# openSX70_ALADDIN_V391_20180125.net
KiCad netlist of a schematic drawn in EAGLE
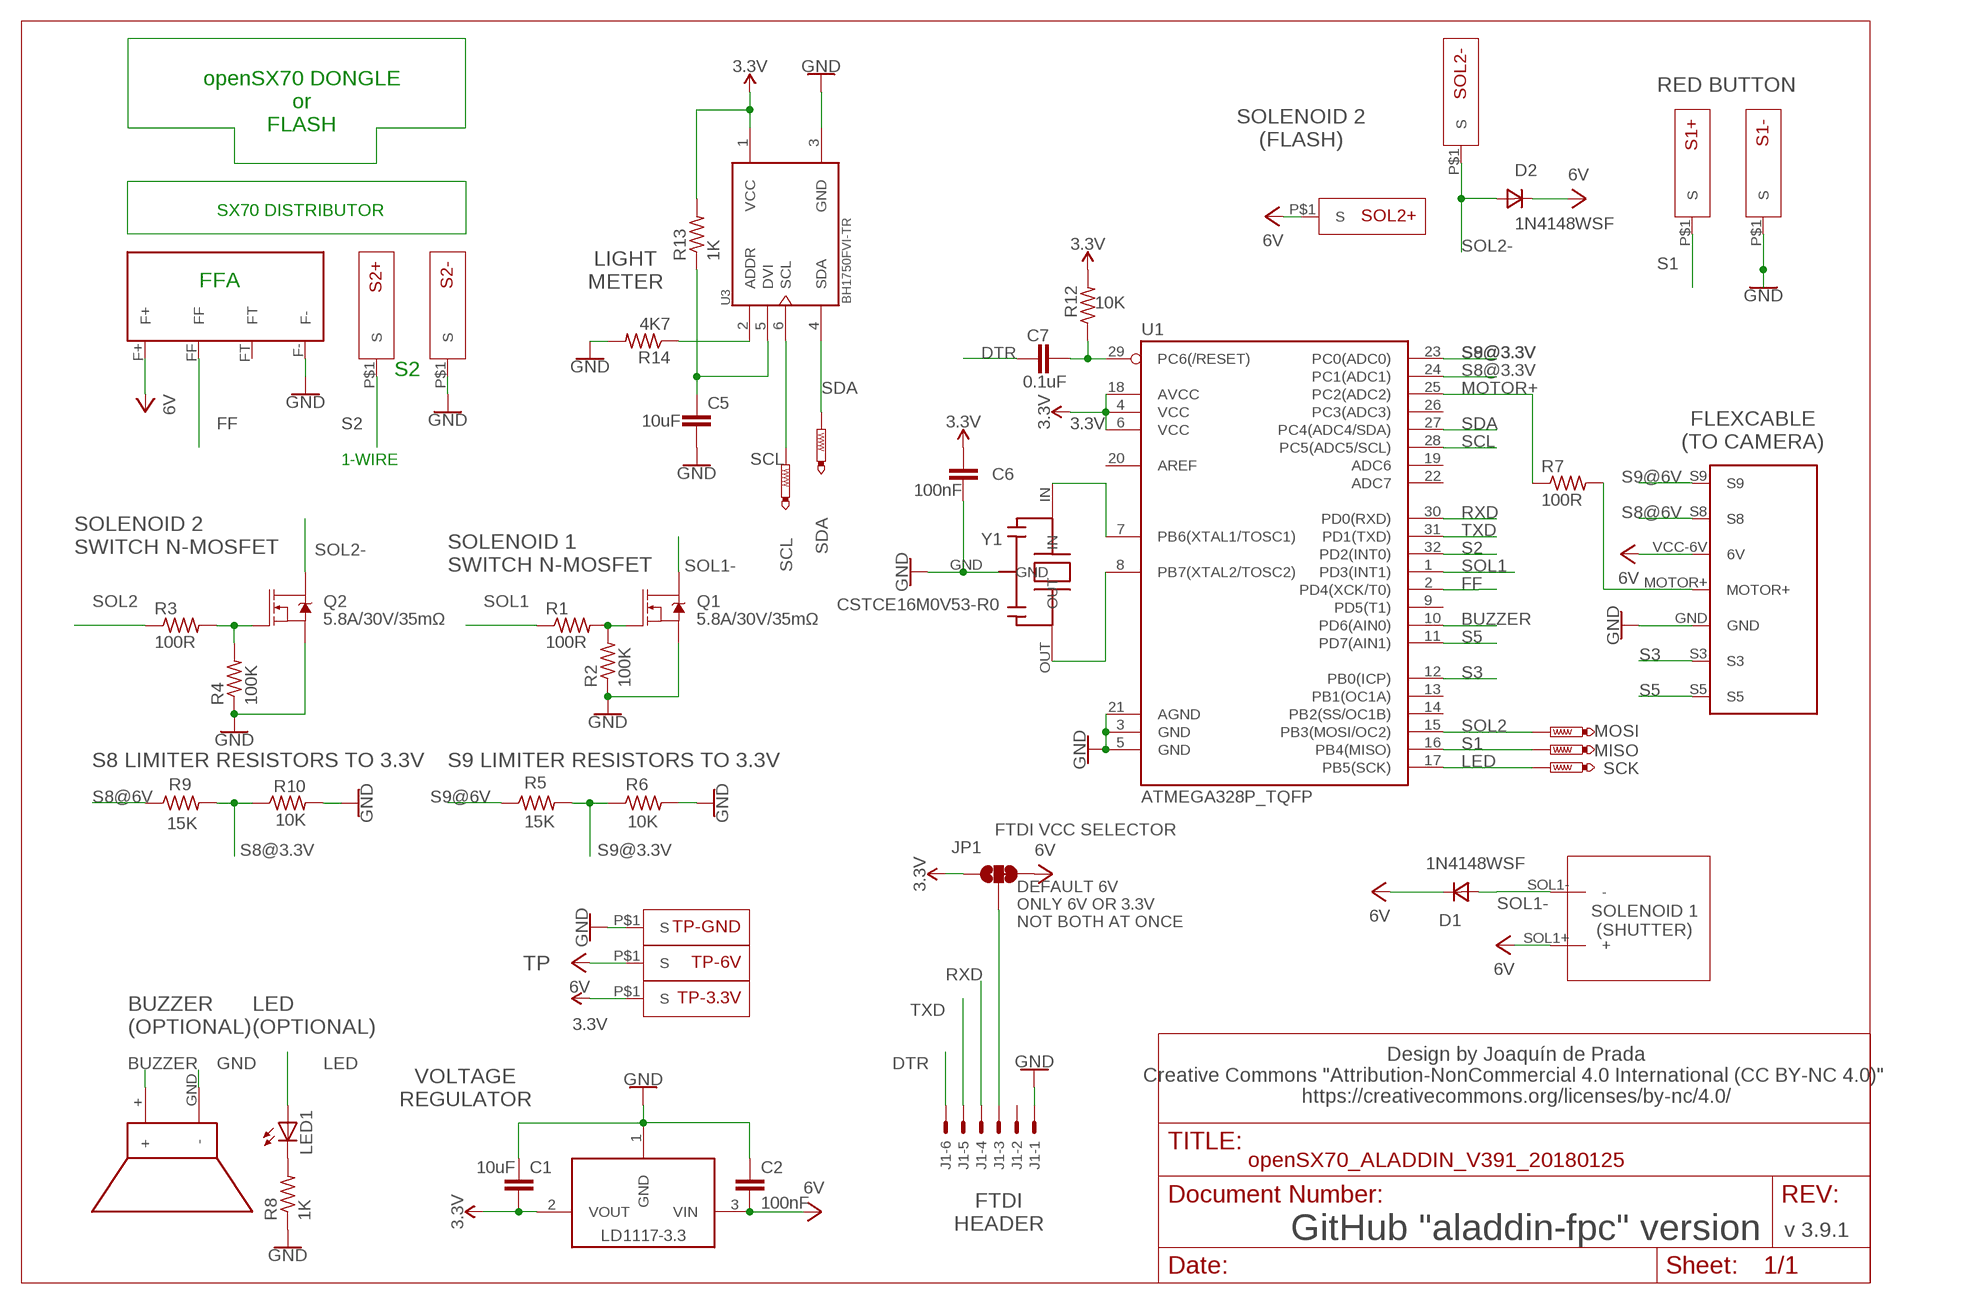
[diagram p0: schematic, sheet 1]

(export (version "E")
  (design (tool "Eeschema 10.0.6"))
  (components
    (comp (ref "BUZZ1")
      (value "CSET8-5G")
      (footprint "eagle-import:CSET8-5G_PACKAGE")
      (libsource (lib "eagle-import") (part "CSET8-5G"))
    )
    (comp (ref "C1")
      (value "10uF")
      (footprint "eagle-import:0603")
      (libsource (lib "eagle-import") (part "10UF-0603-6.3V-20%"))
    )
    (comp (ref "C2")
      (value "100nF")
      (footprint "eagle-import:C0603K")
      (libsource (lib "eagle-import") (part "C-EUC0603K"))
    )
    (comp (ref "C5")
      (value "10uF")
      (footprint "eagle-import:0603")
      (libsource (lib "eagle-import") (part "10UF-0603-6.3V-20%"))
    )
    (comp (ref "C6")
      (value "100nF")
      (footprint "eagle-import:C0603")
      (libsource (lib "eagle-import") (part "C-EUC0603"))
    )
    (comp (ref "C7")
      (value "0.1uF")
      (footprint "eagle-import:0603")
      (libsource (lib "eagle-import") (part "0.1UF-0603-25V-(+80/-20%)"))
    )
    (comp (ref "D1")
      (value "1N4148WSF")
      (footprint "eagle-import:SOD323")
      (fields (field (name "MPN") "CDSOD323-T05C"))
      (libsource (lib "eagle-import") (part "DSOD323"))
    )
    (comp (ref "D2")
      (value "1N4148WSF")
      (footprint "eagle-import:SOD323")
      (fields (field (name "MPN") "CDSOD323-T05C"))
      (libsource (lib "eagle-import") (part "DSOD323"))
    )
    (comp (ref "J1")
      (value "GND")
      (footprint "eagle-import:XF2L-0625-1")
      (fields (field (name "MF") "OMRON COMPONENTS USA") (field (name "MPN") "XF2L-0625-1"))
      (libsource (lib "eagle-import") (part "XF2-06?25-1L"))
    )
    (comp (ref "JP1")
      (value "FTDI VCC SELECTOR")
      (footprint "eagle-import:SMT-JUMPER_3_1-NC_TRACE_SILK")
      (libsource (lib "eagle-import") (part "JUMPER-SMT_3_1-NC_TRACE_SILK"))
    )
    (comp (ref "LD11172.5V")
      (value "LD1117 2.5V")
      (footprint "eagle-import:SOT223")
      (fields (field (name "MF") "Advanced Monolithic Systems") (field (name "MP") "AMS1117-5.0"))
      (libsource (lib "eagle-import") (part "LD1117-3.3"))
    )
    (comp (ref "LED1")
      (value "LEDCHIPLED_0805")
      (footprint "eagle-import:CHIPLED_0805")
      (libsource (lib "eagle-import") (part "LEDCHIPLED_0805"))
    )
    (comp (ref "MISO")
      (value "PTR1TP08R")
      (footprint "eagle-import:TP08R")
      (libsource (lib "eagle-import") (part "PTR1TP08R"))
    )
    (comp (ref "MOSI")
      (value "PTR1TP08R")
      (footprint "eagle-import:TP08R")
      (libsource (lib "eagle-import") (part "PTR1TP08R"))
    )
    (comp (ref "Q1")
      (value "5.8A/30V/35mΩ")
      (footprint "eagle-import:SOT23-3")
      (libsource (lib "eagle-import") (part "MOSFET-NCH-AO3404A"))
    )
    (comp (ref "Q2")
      (value "5.8A/30V/35mΩ")
      (footprint "eagle-import:SOT23-3")
      (libsource (lib "eagle-import") (part "MOSFET-NCH-AO3404A"))
    )
    (comp (ref "R1")
      (value "100R")
      (footprint "eagle-import:R0603")
      (libsource (lib "eagle-import") (part "R-US_R0603"))
    )
    (comp (ref "R2")
      (value "100K")
      (footprint "eagle-import:R0603")
      (libsource (lib "eagle-import") (part "R-US_R0603"))
    )
    (comp (ref "R3")
      (value "100R")
      (footprint "eagle-import:R0603")
      (libsource (lib "eagle-import") (part "R-US_R0603"))
    )
    (comp (ref "R4")
      (value "100K")
      (footprint "eagle-import:R0603")
      (libsource (lib "eagle-import") (part "R-US_R0603"))
    )
    (comp (ref "R5")
      (value "15K")
      (footprint "eagle-import:R0603")
      (libsource (lib "eagle-import") (part "R-US_R0603"))
    )
    (comp (ref "R6")
      (value "10K")
      (footprint "eagle-import:R0603")
      (libsource (lib "eagle-import") (part "R-US_R0603"))
    )
    (comp (ref "R7")
      (value "100R")
      (footprint "eagle-import:R0603")
      (libsource (lib "eagle-import") (part "R-US_R0603"))
    )
    (comp (ref "R8")
      (value "1K")
      (footprint "eagle-import:R0603")
      (libsource (lib "eagle-import") (part "R-US_R0603"))
    )
    (comp (ref "R9")
      (value "15K")
      (footprint "eagle-import:R0603")
      (libsource (lib "eagle-import") (part "R-US_R0603"))
    )
    (comp (ref "R10")
      (value "10K")
      (footprint "eagle-import:R0603")
      (libsource (lib "eagle-import") (part "R-US_R0603"))
    )
    (comp (ref "R12")
      (value "10K")
      (footprint "eagle-import:R0603")
      (libsource (lib "eagle-import") (part "R-US_R0603"))
    )
    (comp (ref "R13")
      (value "1K")
      (footprint "eagle-import:R0603")
      (libsource (lib "eagle-import") (part "R-US_R0603"))
    )
    (comp (ref "R14")
      (value "4K7")
      (footprint "eagle-import:R0603")
      (libsource (lib "eagle-import") (part "R-US_R0603"))
    )
    (comp (ref "S1+")
      (value "SX70-S-PAD-NEW")
      (footprint "eagle-import:SX70-S-PAD2")
      (libsource (lib "eagle-import") (part "SX70-S-PAD-NEW"))
    )
    (comp (ref "S1-")
      (value "SX70-S-PAD-NEW")
      (footprint "eagle-import:SX70-S-PAD2")
      (libsource (lib "eagle-import") (part "SX70-S-PAD-NEW"))
    )
    (comp (ref "S2+")
      (value "SX70-S-PAD-NEW")
      (footprint "eagle-import:SX70-S-PAD2")
      (libsource (lib "eagle-import") (part "SX70-S-PAD-NEW"))
    )
    (comp (ref "S2-")
      (value "SX70-S-PAD-NEW")
      (footprint "eagle-import:SX70-S-PAD2")
      (libsource (lib "eagle-import") (part "SX70-S-PAD-NEW"))
    )
    (comp (ref "SCK")
      (value "PTR1TP08R")
      (footprint "eagle-import:TP08R")
      (libsource (lib "eagle-import") (part "PTR1TP08R"))
    )
    (comp (ref "SCL")
      (value "PTR1TP08R")
      (footprint "eagle-import:TP08R")
      (libsource (lib "eagle-import") (part "PTR1TP08R"))
    )
    (comp (ref "SDA")
      (value "PTR1TP08R")
      (footprint "eagle-import:TP08R")
      (libsource (lib "eagle-import") (part "PTR1TP08R"))
    )
    (comp (ref "SOL1")
      (value "SX70-SOLENOID1-2PADS")
      (footprint "eagle-import:SX70-SOLENOID1-2")
      (libsource (lib "eagle-import") (part "SX70-SOLENOID1-2PADS"))
    )
    (comp (ref "SOL2+")
      (value "SX70-S-PAD-NEW")
      (footprint "eagle-import:SX70-S-PAD2")
      (libsource (lib "eagle-import") (part "SX70-S-PAD-NEW"))
    )
    (comp (ref "SOL2-")
      (value "SX70-S-PAD-NEW")
      (footprint "eagle-import:SX70-S-PAD2")
      (libsource (lib "eagle-import") (part "SX70-S-PAD-NEW"))
    )
    (comp (ref "TP-3.3V")
      (value "SX70-S-PAD-NEW")
      (footprint "eagle-import:SX70-S-PAD2")
      (libsource (lib "eagle-import") (part "SX70-S-PAD-NEW"))
    )
    (comp (ref "TP-6V")
      (value "SX70-S-PAD-NEW")
      (footprint "eagle-import:SX70-S-PAD2")
      (libsource (lib "eagle-import") (part "SX70-S-PAD-NEW"))
    )
    (comp (ref "TP-GND")
      (value "SX70-S-PAD-NEW")
      (footprint "eagle-import:SX70-S-PAD2")
      (libsource (lib "eagle-import") (part "SX70-S-PAD-NEW"))
    )
    (comp (ref "U$1")
      (value "SX70-7-PAD")
      (footprint "eagle-import:SX70-7-PAD")
      (libsource (lib "eagle-import") (part "SX70-7-PAD"))
    )
    (comp (ref "U$2")
      (value "FFA")
      (footprint "eagle-import:FFA-PAD-PACKAGE")
      (libsource (lib "eagle-import") (part "SX70-FFA-PAD"))
    )
    (comp (ref "U1")
      (value "ATMEGA328P_TQFP")
      (footprint "eagle-import:TQFP32-08")
      (libsource (lib "eagle-import") (part "ATMEGA328P_TQFP"))
    )
    (comp (ref "U3")
      (value "BH1750FVI-TR")
      (footprint "eagle-import:SOTFL50P300X75-6N")
      (fields (field (name "MF") "Rohm"))
      (libsource (lib "eagle-import") (part "BH1750FVI-TR"))
    )
    (comp (ref "Y1")
      (value "CSTCE16M0V53-R0")
      (footprint "eagle-import:CFP95P160X100-3N")
      (fields (field (name "MF") "Murata"))
      (libsource (lib "eagle-import") (part "CSTCE16M0V53-R0"))
    )
  )
  (nets
    (net (code "1") (name "/BUZZER") (class "Default")
      (node (ref "BUZZ1") (pin "+") (pinfunction "+_+") (pintype "bidirectional"))
      (node (ref "U1") (pin "10") (pinfunction "PD6(AIN0)_10") (pintype "bidirectional"))
    )
    (net (code "2") (name "/DTR") (class "Default")
      (node (ref "C7") (pin "1") (pinfunction "1_1") (pintype "passive"))
      (node (ref "J1") (pin "6") (pinfunction "MS_6") (pintype "passive"))
    )
    (net (code "3") (name "/FF") (class "Default")
      (node (ref "U$2") (pin "FF") (pinfunction "FF_FF") (pintype "bidirectional"))
      (node (ref "U1") (pin "2") (pinfunction "PD4(XCK/T0)_2") (pintype "bidirectional"))
    )
    (net (code "4") (name "/LED") (class "Default")
      (node (ref "LED1") (pin "A") (pinfunction "A_A") (pintype "passive"))
      (node (ref "SCK") (pin "TP") (pinfunction "TP_TP") (pintype "input"))
      (node (ref "U1") (pin "17") (pinfunction "PB5(SCK)_17") (pintype "bidirectional"))
    )
    (net (code "5") (name "/MOTOR+") (class "Default")
      (node (ref "R7") (pin "1") (pinfunction "1_1") (pintype "passive"))
      (node (ref "U1") (pin "25") (pinfunction "PC2(ADC2)_25") (pintype "bidirectional"))
    )
    (net (code "6") (name "/RXD") (class "Default")
      (node (ref "J1") (pin "4") (pinfunction "MS_4") (pintype "passive"))
      (node (ref "U1") (pin "30") (pinfunction "PD0(RXD)_30") (pintype "bidirectional"))
    )
    (net (code "7") (name "/S1") (class "Default")
      (node (ref "MISO") (pin "TP") (pinfunction "TP_TP") (pintype "input"))
      (node (ref "S1+") (pin "P$1") (pinfunction "S_P$1") (pintype "bidirectional"))
      (node (ref "U1") (pin "16") (pinfunction "PB4(MISO)_16") (pintype "bidirectional"))
    )
    (net (code "8") (name "/S2") (class "Default")
      (node (ref "S2+") (pin "P$1") (pinfunction "S_P$1") (pintype "bidirectional"))
      (node (ref "U1") (pin "32") (pinfunction "PD2(INT0)_32") (pintype "bidirectional"))
    )
    (net (code "9") (name "/S3") (class "Default")
      (node (ref "U$1") (pin "S3") (pinfunction "S3_S3") (pintype "bidirectional"))
      (node (ref "U1") (pin "12") (pinfunction "PB0(ICP)_12") (pintype "bidirectional"))
    )
    (net (code "10") (name "/S5") (class "Default")
      (node (ref "U$1") (pin "S5") (pinfunction "S5_S5") (pintype "bidirectional"))
      (node (ref "U1") (pin "11") (pinfunction "PD7(AIN1)_11") (pintype "bidirectional"))
    )
    (net (code "11") (name "/S8@3.3V") (class "Default")
      (node (ref "R10") (pin "1") (pinfunction "1_1") (pintype "passive"))
      (node (ref "R9") (pin "2") (pinfunction "2_2") (pintype "passive"))
      (node (ref "U1") (pin "24") (pinfunction "PC1(ADC1)_24") (pintype "bidirectional"))
    )
    (net (code "12") (name "/S8@6V") (class "Default")
      (node (ref "R9") (pin "1") (pinfunction "1_1") (pintype "passive"))
      (node (ref "U$1") (pin "S8") (pinfunction "S8_S8") (pintype "bidirectional"))
    )
    (net (code "13") (name "/S9@3.3V") (class "Default")
      (node (ref "R5") (pin "2") (pinfunction "2_2") (pintype "passive"))
      (node (ref "R6") (pin "1") (pinfunction "1_1") (pintype "passive"))
      (node (ref "U1") (pin "23") (pinfunction "PC0(ADC0)_23") (pintype "bidirectional"))
    )
    (net (code "14") (name "/S9@6V") (class "Default")
      (node (ref "R5") (pin "1") (pinfunction "1_1") (pintype "passive"))
      (node (ref "U$1") (pin "S9") (pinfunction "S9_S9") (pintype "bidirectional"))
    )
    (net (code "15") (name "/SCL") (class "Default")
      (node (ref "SCL") (pin "TP") (pinfunction "TP_TP") (pintype "input"))
      (node (ref "U1") (pin "28") (pinfunction "PC5(ADC5/SCL)_28") (pintype "bidirectional"))
      (node (ref "U3") (pin "6") (pinfunction "SCL_6") (pintype "input"))
    )
    (net (code "16") (name "/SDA") (class "Default")
      (node (ref "SDA") (pin "TP") (pinfunction "TP_TP") (pintype "input"))
      (node (ref "U1") (pin "27") (pinfunction "PC4(ADC4/SDA)_27") (pintype "bidirectional"))
      (node (ref "U3") (pin "4") (pinfunction "SDA_4") (pintype "bidirectional"))
    )
    (net (code "17") (name "/SOL1") (class "Default")
      (node (ref "R1") (pin "1") (pinfunction "1_1") (pintype "passive"))
      (node (ref "U1") (pin "1") (pinfunction "PD3(INT1)_1") (pintype "bidirectional"))
    )
    (net (code "18") (name "/SOL1-") (class "Default")
      (node (ref "D1") (pin "2") (pinfunction "A_2") (pintype "passive"))
      (node (ref "Q1") (pin "3") (pinfunction "D_3") (pintype "bidirectional"))
      (node (ref "SOL1") (pin "SOL1-") (pinfunction "-_SOL1-") (pintype "bidirectional"))
    )
    (net (code "19") (name "/SOL2") (class "Default")
      (node (ref "MOSI") (pin "TP") (pinfunction "TP_TP") (pintype "input"))
      (node (ref "R3") (pin "1") (pinfunction "1_1") (pintype "passive"))
      (node (ref "U1") (pin "15") (pinfunction "PB3(MOSI/OC2)_15") (pintype "bidirectional"))
    )
    (net (code "20") (name "/SOL2-") (class "Default")
      (node (ref "D2") (pin "2") (pinfunction "A_2") (pintype "passive"))
      (node (ref "Q2") (pin "3") (pinfunction "D_3") (pintype "bidirectional"))
      (node (ref "SOL2-") (pin "P$1") (pinfunction "S_P$1") (pintype "bidirectional"))
    )
    (net (code "21") (name "/TXD") (class "Default")
      (node (ref "J1") (pin "5") (pinfunction "MS_5") (pintype "passive"))
      (node (ref "U1") (pin "31") (pinfunction "PD1(TXD)_31") (pintype "bidirectional"))
    )
    (net (code "22") (name "3.3V") (class "Default")
      (node (ref "C1") (pin "2") (pinfunction "2_2") (pintype "passive"))
      (node (ref "C6") (pin "1") (pinfunction "1_1") (pintype "passive"))
      (node (ref "JP1") (pin "1") (pinfunction "1_1") (pintype "passive"))
      (node (ref "LD11172.5V") (pin "2") (pinfunction "VOUT_2") (pintype "bidirectional"))
      (node (ref "R12") (pin "2") (pinfunction "2_2") (pintype "passive"))
      (node (ref "R13") (pin "2") (pinfunction "2_2") (pintype "passive"))
      (node (ref "TP-3.3V") (pin "P$1") (pinfunction "S_P$1") (pintype "bidirectional"))
      (node (ref "U1") (pin "18") (pinfunction "AVCC_18") (pintype "bidirectional"))
      (node (ref "U1") (pin "4") (pinfunction "VCC_4") (pintype "bidirectional"))
      (node (ref "U1") (pin "6") (pinfunction "VCC_6") (pintype "bidirectional"))
      (node (ref "U3") (pin "1") (pinfunction "VCC_1") (pintype "power_in"))
    )
    (net (code "23") (name "6V") (class "Default")
      (node (ref "C2") (pin "2") (pinfunction "2_2") (pintype "passive"))
      (node (ref "D1") (pin "1") (pinfunction "C_1") (pintype "passive"))
      (node (ref "D2") (pin "1") (pinfunction "C_1") (pintype "passive"))
      (node (ref "JP1") (pin "3") (pinfunction "3_3") (pintype "passive"))
      (node (ref "LD11172.5V") (pin "3") (pinfunction "VIN_3") (pintype "bidirectional"))
      (node (ref "SOL1") (pin "SOL1+") (pinfunction "+_SOL1+") (pintype "bidirectional"))
      (node (ref "SOL2+") (pin "P$1") (pinfunction "S_P$1") (pintype "bidirectional"))
      (node (ref "TP-6V") (pin "P$1") (pinfunction "S_P$1") (pintype "bidirectional"))
      (node (ref "U$1") (pin "VCC-6V") (pinfunction "6V_VCC-6V") (pintype "bidirectional"))
      (node (ref "U$2") (pin "F+") (pinfunction "F+_F+") (pintype "bidirectional"))
    )
    (net (code "24") (name "GND") (class "Default")
      (node (ref "BUZZ1") (pin "GND") (pinfunction "-_GND") (pintype "bidirectional"))
      (node (ref "C1") (pin "1") (pinfunction "1_1") (pintype "passive"))
      (node (ref "C2") (pin "1") (pinfunction "1_1") (pintype "passive"))
      (node (ref "C5") (pin "2") (pinfunction "2_2") (pintype "passive"))
      (node (ref "C6") (pin "2") (pinfunction "2_2") (pintype "passive"))
      (node (ref "J1") (pin "1") (pinfunction "MS_1") (pintype "passive"))
      (node (ref "LD11172.5V") (pin "1") (pinfunction "GND_1") (pintype "bidirectional"))
      (node (ref "Q1") (pin "2") (pinfunction "S_2") (pintype "bidirectional"))
      (node (ref "Q2") (pin "2") (pinfunction "S_2") (pintype "bidirectional"))
      (node (ref "R10") (pin "2") (pinfunction "2_2") (pintype "passive"))
      (node (ref "R14") (pin "2") (pinfunction "2_2") (pintype "passive"))
      (node (ref "R2") (pin "1") (pinfunction "1_1") (pintype "passive"))
      (node (ref "R4") (pin "1") (pinfunction "1_1") (pintype "passive"))
      (node (ref "R6") (pin "2") (pinfunction "2_2") (pintype "passive"))
      (node (ref "R8") (pin "1") (pinfunction "1_1") (pintype "passive"))
      (node (ref "S1-") (pin "P$1") (pinfunction "S_P$1") (pintype "bidirectional"))
      (node (ref "S2-") (pin "P$1") (pinfunction "S_P$1") (pintype "bidirectional"))
      (node (ref "TP-GND") (pin "P$1") (pinfunction "S_P$1") (pintype "bidirectional"))
      (node (ref "U$1") (pin "GND") (pinfunction "GND_GND") (pintype "bidirectional"))
      (node (ref "U$2") (pin "F-") (pinfunction "F-_F-") (pintype "bidirectional"))
      (node (ref "U1") (pin "21") (pinfunction "AGND_21") (pintype "bidirectional"))
      (node (ref "U1") (pin "3") (pinfunction "GND_3") (pintype "bidirectional"))
      (node (ref "U1") (pin "5") (pinfunction "GND_5") (pintype "bidirectional"))
      (node (ref "U3") (pin "3") (pinfunction "GND_3") (pintype "power_in"))
      (node (ref "Y1") (pin "GND") (pinfunction "GND_GND") (pintype "passive"))
    )
    (net (code "25") (name "Net-(J1C-MS)") (class "Default")
      (node (ref "J1") (pin "3") (pinfunction "MS_3") (pintype "passive"))
      (node (ref "JP1") (pin "2") (pinfunction "2_2") (pintype "passive"))
    )
    (net (code "26") (name "Net-(LED1-PadC)") (class "Default")
      (node (ref "LED1") (pin "C") (pinfunction "C_C") (pintype "passive"))
      (node (ref "R8") (pin "2") (pinfunction "2_2") (pintype "passive"))
    )
    (net (code "27") (name "Net-(Q1-G)") (class "Default")
      (node (ref "Q1") (pin "1") (pinfunction "G_1") (pintype "bidirectional"))
      (node (ref "R1") (pin "2") (pinfunction "2_2") (pintype "passive"))
      (node (ref "R2") (pin "2") (pinfunction "2_2") (pintype "passive"))
    )
    (net (code "28") (name "Net-(Q2-G)") (class "Default")
      (node (ref "Q2") (pin "1") (pinfunction "G_1") (pintype "bidirectional"))
      (node (ref "R3") (pin "2") (pinfunction "2_2") (pintype "passive"))
      (node (ref "R4") (pin "2") (pinfunction "2_2") (pintype "passive"))
    )
    (net (code "29") (name "Net-(R7-Pad2)") (class "Default")
      (node (ref "R7") (pin "2") (pinfunction "2_2") (pintype "passive"))
      (node (ref "U$1") (pin "MOTOR+") (pinfunction "MOTOR+_MOTOR+") (pintype "bidirectional"))
    )
    (net (code "30") (name "Net-(U1-PB6(XTAL1{slash}TOSC1))") (class "Default")
      (node (ref "U1") (pin "7") (pinfunction "PB6(XTAL1/TOSC1)_7") (pintype "bidirectional"))
      (node (ref "Y1") (pin "IN") (pinfunction "IN_IN") (pintype "input"))
    )
    (net (code "31") (name "Net-(U1-PB7(XTAL2{slash}TOSC2))") (class "Default")
      (node (ref "U1") (pin "8") (pinfunction "PB7(XTAL2/TOSC2)_8") (pintype "bidirectional"))
      (node (ref "Y1") (pin "OUT") (pinfunction "OUT_OUT") (pintype "output"))
    )
    (net (code "32") (name "Net-(U1-PC6({slash}RESET))") (class "Default")
      (node (ref "C7") (pin "2") (pinfunction "2_2") (pintype "passive"))
      (node (ref "R12") (pin "1") (pinfunction "1_1") (pintype "passive"))
      (node (ref "U1") (pin "29") (pinfunction "PC6(/RESET)_29") (pintype "bidirectional"))
    )
    (net (code "33") (name "Net-(U3-ADDR)") (class "Default")
      (node (ref "R14") (pin "1") (pinfunction "1_1") (pintype "passive"))
      (node (ref "U3") (pin "2") (pinfunction "ADDR_2") (pintype "input"))
    )
    (net (code "34") (name "Net-(U3-DVI)") (class "Default")
      (node (ref "C5") (pin "1") (pinfunction "1_1") (pintype "passive"))
      (node (ref "R13") (pin "1") (pinfunction "1_1") (pintype "passive"))
      (node (ref "U3") (pin "5") (pinfunction "DVI_5") (pintype "input"))
    )
    (net (code "35") (name "unconnected-(J1B-MS-Pad2)") (class "Default")
      (node (ref "J1") (pin "2") (pinfunction "MS_2") (pintype "passive"))
    )
    (net (code "36") (name "unconnected-(U$2-PadFT)") (class "Default")
      (node (ref "U$2") (pin "FT") (pinfunction "FT_FT") (pintype "bidirectional"))
    )
    (net (code "37") (name "unconnected-(U1-ADC6-Pad19)") (class "Default")
      (node (ref "U1") (pin "19") (pinfunction "ADC6_19") (pintype "bidirectional"))
    )
    (net (code "38") (name "unconnected-(U1-ADC7-Pad22)") (class "Default")
      (node (ref "U1") (pin "22") (pinfunction "ADC7_22") (pintype "bidirectional"))
    )
    (net (code "39") (name "unconnected-(U1-AREF-Pad20)") (class "Default")
      (node (ref "U1") (pin "20") (pinfunction "AREF_20") (pintype "bidirectional"))
    )
    (net (code "40") (name "unconnected-(U1-PB1(OC1A)-Pad13)") (class "Default")
      (node (ref "U1") (pin "13") (pinfunction "PB1(OC1A)_13") (pintype "bidirectional"))
    )
    (net (code "41") (name "unconnected-(U1-PB2(SS{slash}OC1B)-Pad14)") (class "Default")
      (node (ref "U1") (pin "14") (pinfunction "PB2(SS/OC1B)_14") (pintype "bidirectional"))
    )
    (net (code "42") (name "unconnected-(U1-PC3(ADC3)-Pad26)") (class "Default")
      (node (ref "U1") (pin "26") (pinfunction "PC3(ADC3)_26") (pintype "bidirectional"))
    )
    (net (code "43") (name "unconnected-(U1-PD5(T1)-Pad9)") (class "Default")
      (node (ref "U1") (pin "9") (pinfunction "PD5(T1)_9") (pintype "bidirectional"))
    )
  )
)
